# WiFly-BoosterPack-RevA1.net
KiCad netlist of a schematic drawn in EAGLE
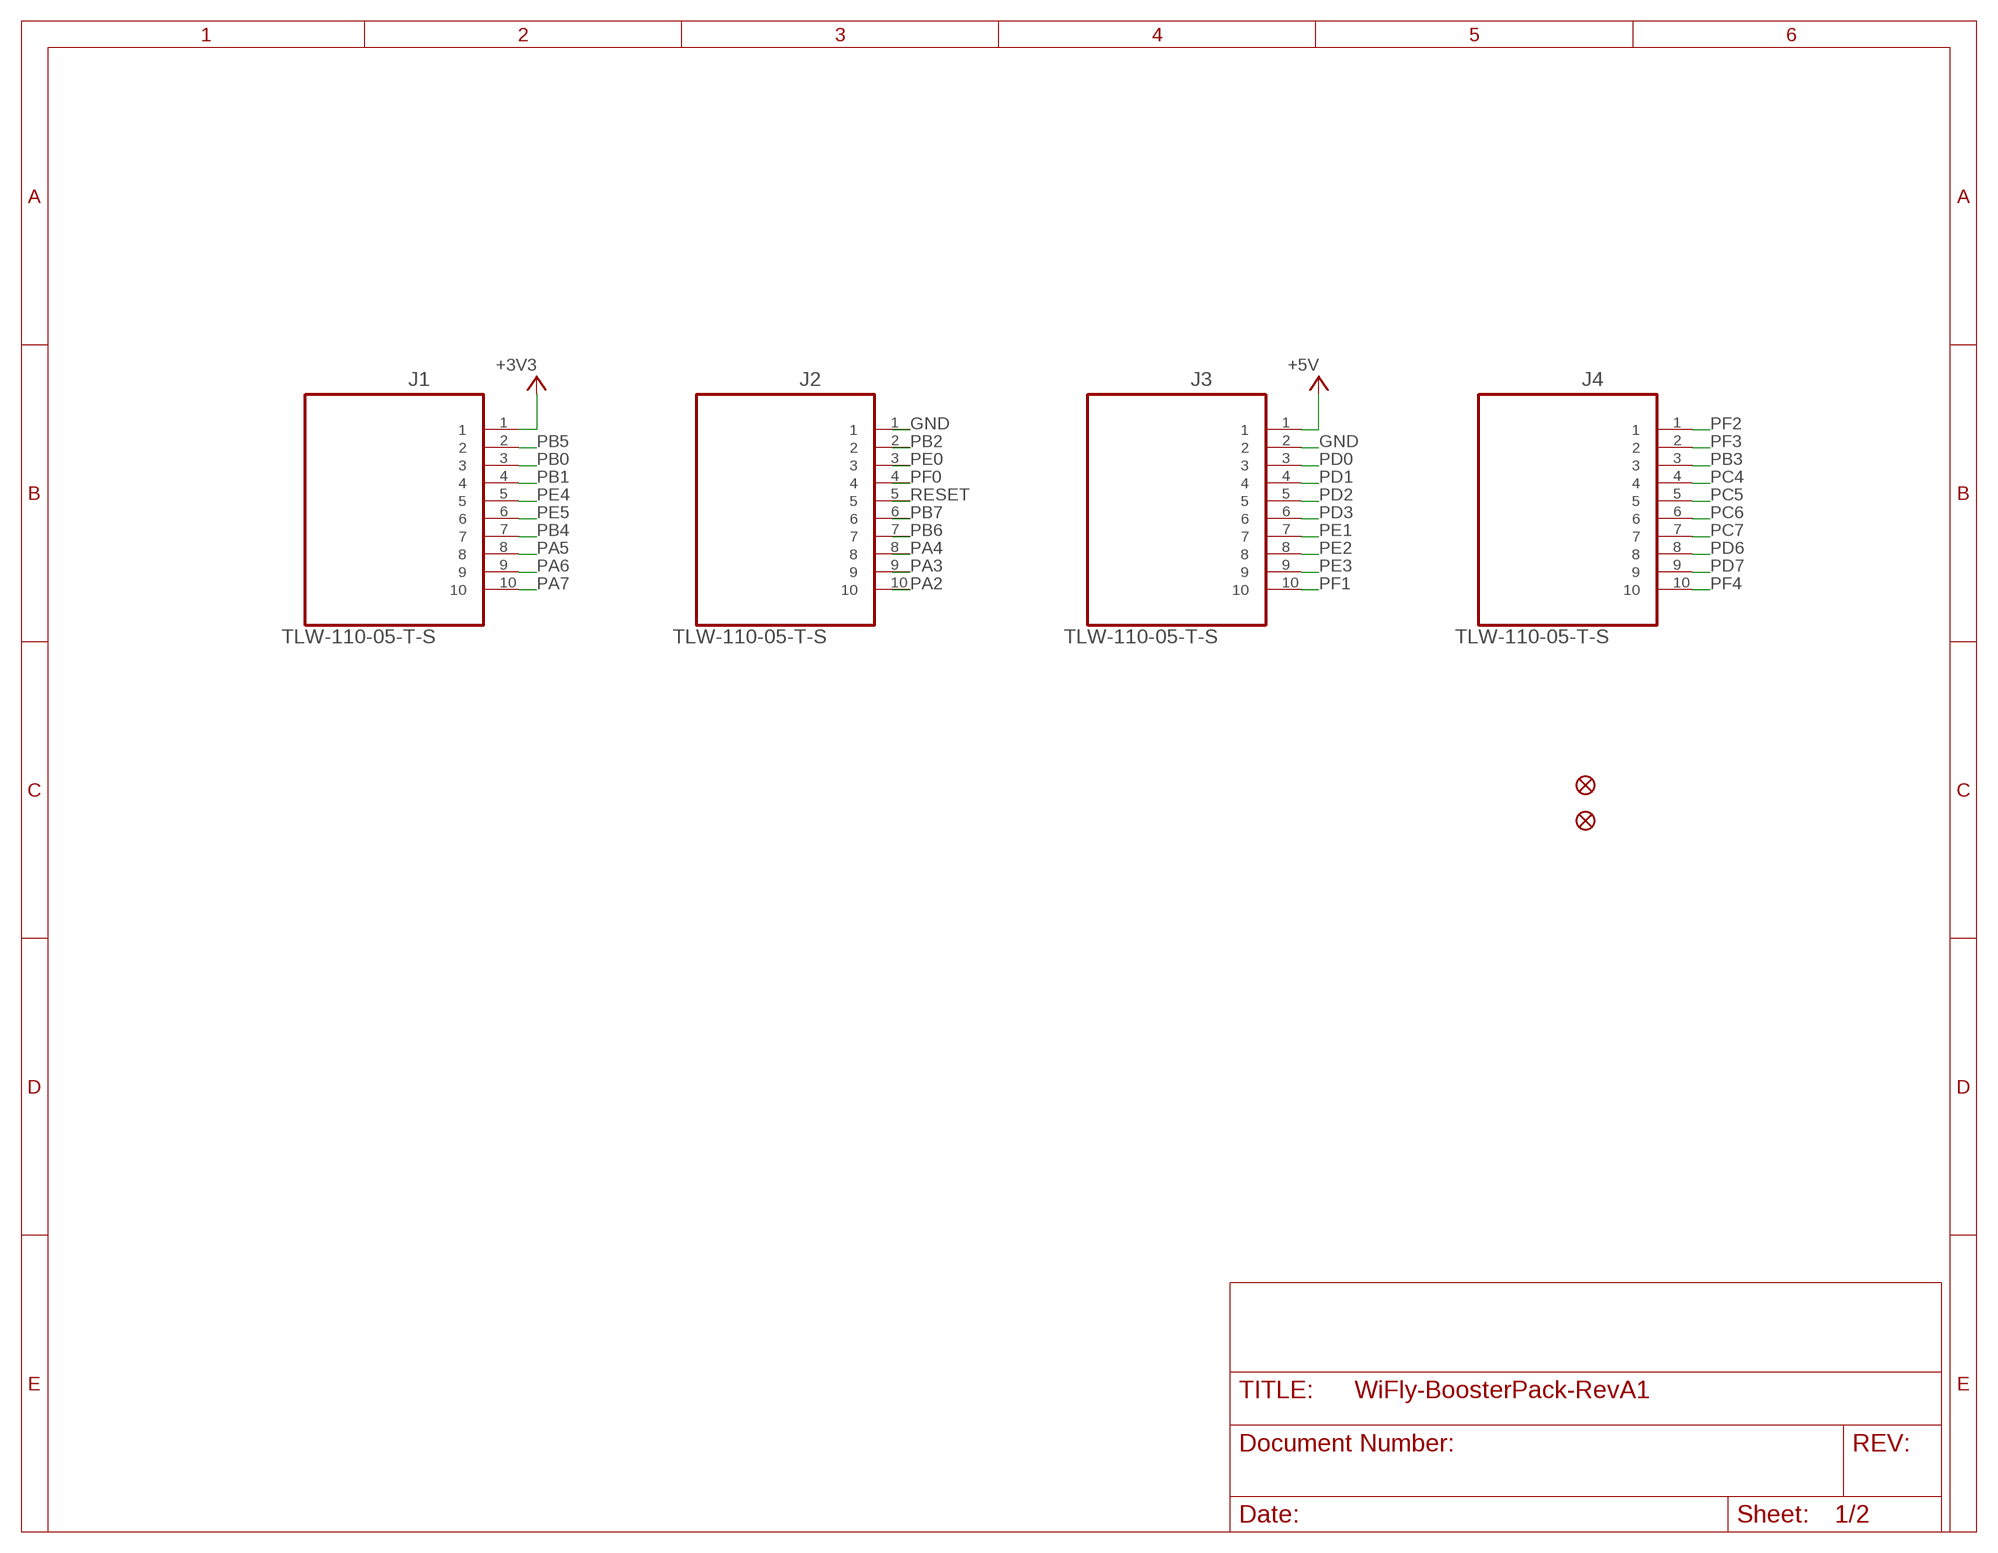
[diagram p0: schematic, sheet 1]
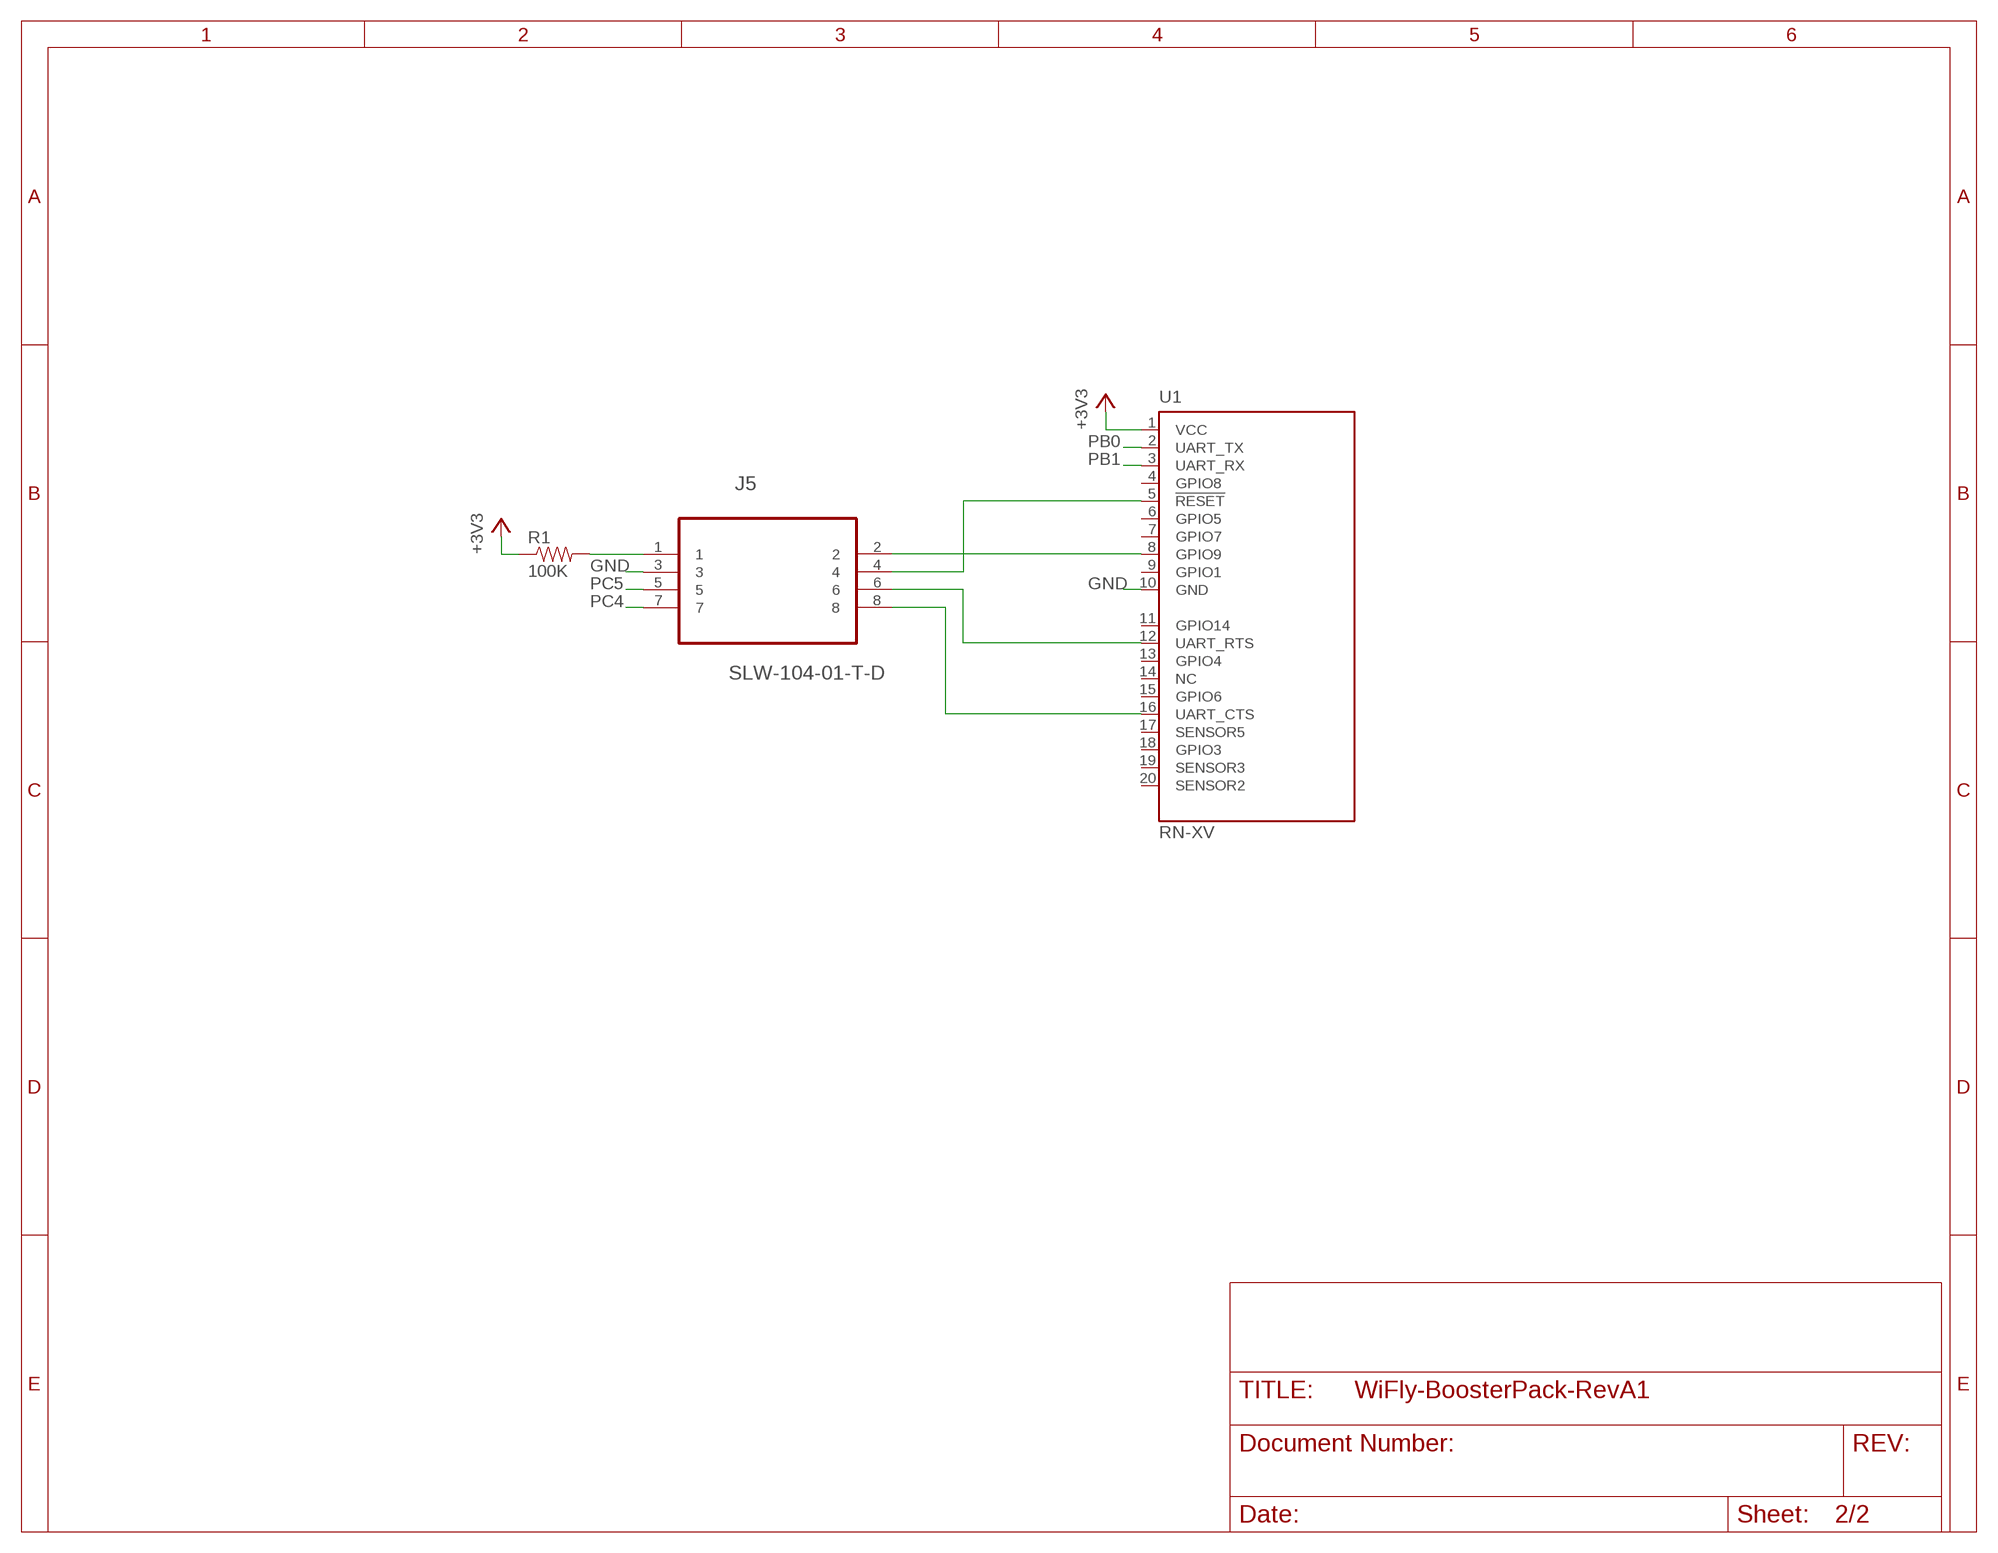
[diagram p1: schematic, sheet 2]

(export (version "E")
  (design (tool "Eeschema 10.0.6"))
  (components
    (comp (ref "FID1")
      (value "FIDUCIAL1X2")
      (footprint "eagle-import:FIDUCIAL-1X2")
      (libsource (lib "eagle-import") (part "FIDUCIAL1X2"))
    )
    (comp (ref "FID2")
      (value "FIDUCIAL1X2")
      (footprint "eagle-import:FIDUCIAL-1X2")
      (libsource (lib "eagle-import") (part "FIDUCIAL1X2"))
    )
    (comp (ref "J1")
      (value "TLW-110-05-T-S")
      (footprint "eagle-import:SAMTEC_TLW-110-05-T-S")
      (libsource (lib "eagle-import") (part "TLW-110-05-T-S"))
    )
    (comp (ref "J2")
      (value "TLW-110-05-T-S")
      (footprint "eagle-import:SAMTEC_TLW-110-05-T-S")
      (fields
        (field (name "MPN") "TLW-110-05-T-S")
        (field (name "OC_FARNELL") "-")
        (field (name "OC_NEWARK") "12P0439")
        (field (name "PACKAGE") "CONN HEADER 10 POS .100 inch")
        (field (name "SUPPLIER") "SAMTEC")
      )
      (libsource (lib "eagle-import") (part "TLW-110-05-T-S"))
    )
    (comp (ref "J3")
      (value "TLW-110-05-T-S")
      (footprint "eagle-import:SAMTEC_TLW-110-05-T-S")
      (fields
        (field (name "MPN") "TLW-110-05-T-S")
        (field (name "OC_FARNELL") "-")
        (field (name "OC_NEWARK") "12P0439")
        (field (name "PACKAGE") "CONN HEADER 10 POS .100 inch")
        (field (name "SUPPLIER") "SAMTEC")
      )
      (libsource (lib "eagle-import") (part "TLW-110-05-T-S"))
    )
    (comp (ref "J4")
      (value "TLW-110-05-T-S")
      (footprint "eagle-import:SAMTEC_TLW-110-05-T-S")
      (fields
        (field (name "MPN") "TLW-110-05-T-S")
        (field (name "OC_FARNELL") "-")
        (field (name "OC_NEWARK") "12P0439")
        (field (name "PACKAGE") "CONN HEADER 10 POS .100 inch")
        (field (name "SUPPLIER") "SAMTEC")
      )
      (libsource (lib "eagle-import") (part "TLW-110-05-T-S"))
    )
    (comp (ref "J5")
      (value "SLW-104-01-T-D")
      (footprint "eagle-import:SAMTEC_SLW-104-01-T-D")
      (libsource (lib "eagle-import") (part "SLW-104-01-T-D"))
    )
    (comp (ref "R1")
      (value "100K")
      (footprint "eagle-import:AXIAL-0.3")
      (libsource (lib "eagle-import") (part "RESISTORAXIAL-0.3"))
    )
    (comp (ref "U1")
      (value "RN-XV")
      (footprint "eagle-import:RN-VX")
      (libsource (lib "eagle-import") (part "RN-XV"))
    )
  )
  (nets
    (net (code "1") (name "+3V3") (class "Default")
      (node (ref "J1") (pin "1") (pinfunction "1_1") (pintype "passive"))
      (node (ref "R1") (pin "P$1") (pinfunction "1_P$1") (pintype "passive"))
      (node (ref "U1") (pin "1") (pinfunction "VCC_1") (pintype "power_in"))
    )
    (net (code "2") (name "+5V") (class "Default")
      (node (ref "J3") (pin "1") (pinfunction "1_1") (pintype "passive"))
    )
    (net (code "3") (name "GND") (class "Default")
      (node (ref "J2") (pin "1") (pinfunction "1_1") (pintype "passive"))
      (node (ref "J3") (pin "2") (pinfunction "2_2") (pintype "passive"))
      (node (ref "J5") (pin "3") (pinfunction "3_3") (pintype "passive"))
      (node (ref "U1") (pin "10") (pinfunction "GND_10") (pintype "power_in"))
    )
    (net (code "4") (name "Net-(R1-2)") (class "Default")
      (node (ref "J5") (pin "1") (pinfunction "1_1") (pintype "passive"))
      (node (ref "R1") (pin "P$2") (pinfunction "2_P$2") (pintype "passive"))
    )
    (net (code "5") (name "Net-(U1-GPIO9)") (class "Default")
      (node (ref "J5") (pin "2") (pinfunction "2_2") (pintype "passive"))
      (node (ref "U1") (pin "8") (pinfunction "GPIO9_8") (pintype "bidirectional"))
    )
    (net (code "6") (name "Net-(U1-UART_CTS)") (class "Default")
      (node (ref "J5") (pin "8") (pinfunction "8_8") (pintype "passive"))
      (node (ref "U1") (pin "16") (pinfunction "UART_CTS_16") (pintype "input"))
    )
    (net (code "7") (name "Net-(U1-UART_RTS)") (class "Default")
      (node (ref "J5") (pin "6") (pinfunction "6_6") (pintype "passive"))
      (node (ref "U1") (pin "12") (pinfunction "UART_RTS_12") (pintype "output"))
    )
    (net (code "8") (name "Net-(U1-~{RESET})") (class "Default")
      (node (ref "J5") (pin "4") (pinfunction "4_4") (pintype "passive"))
      (node (ref "U1") (pin "5") (pinfunction "~{RESET}_5") (pintype "input"))
    )
    (net (code "9") (name "PA2") (class "Default")
      (node (ref "J2") (pin "10") (pinfunction "10_10") (pintype "passive"))
    )
    (net (code "10") (name "PA3") (class "Default")
      (node (ref "J2") (pin "9") (pinfunction "9_9") (pintype "passive"))
    )
    (net (code "11") (name "PA4") (class "Default")
      (node (ref "J2") (pin "8") (pinfunction "8_8") (pintype "passive"))
    )
    (net (code "12") (name "PA5") (class "Default")
      (node (ref "J1") (pin "8") (pinfunction "8_8") (pintype "passive"))
    )
    (net (code "13") (name "PA6") (class "Default")
      (node (ref "J1") (pin "9") (pinfunction "9_9") (pintype "passive"))
    )
    (net (code "14") (name "PA7") (class "Default")
      (node (ref "J1") (pin "10") (pinfunction "10_10") (pintype "passive"))
    )
    (net (code "15") (name "PB0") (class "Default")
      (node (ref "J1") (pin "3") (pinfunction "3_3") (pintype "passive"))
      (node (ref "U1") (pin "2") (pinfunction "UART_TX_2") (pintype "output"))
    )
    (net (code "16") (name "PB1") (class "Default")
      (node (ref "J1") (pin "4") (pinfunction "4_4") (pintype "passive"))
      (node (ref "U1") (pin "3") (pinfunction "UART_RX_3") (pintype "input"))
    )
    (net (code "17") (name "PB2") (class "Default")
      (node (ref "J2") (pin "2") (pinfunction "2_2") (pintype "passive"))
    )
    (net (code "18") (name "PB3") (class "Default")
      (node (ref "J4") (pin "3") (pinfunction "3_3") (pintype "passive"))
    )
    (net (code "19") (name "PB4") (class "Default")
      (node (ref "J1") (pin "7") (pinfunction "7_7") (pintype "passive"))
    )
    (net (code "20") (name "PB5") (class "Default")
      (node (ref "J1") (pin "2") (pinfunction "2_2") (pintype "passive"))
    )
    (net (code "21") (name "PB6") (class "Default")
      (node (ref "J2") (pin "7") (pinfunction "7_7") (pintype "passive"))
    )
    (net (code "22") (name "PB7") (class "Default")
      (node (ref "J2") (pin "6") (pinfunction "6_6") (pintype "passive"))
    )
    (net (code "23") (name "PC4") (class "Default")
      (node (ref "J4") (pin "4") (pinfunction "4_4") (pintype "passive"))
      (node (ref "J5") (pin "7") (pinfunction "7_7") (pintype "passive"))
    )
    (net (code "24") (name "PC5") (class "Default")
      (node (ref "J4") (pin "5") (pinfunction "5_5") (pintype "passive"))
      (node (ref "J5") (pin "5") (pinfunction "5_5") (pintype "passive"))
    )
    (net (code "25") (name "PC6") (class "Default")
      (node (ref "J4") (pin "6") (pinfunction "6_6") (pintype "passive"))
    )
    (net (code "26") (name "PC7") (class "Default")
      (node (ref "J4") (pin "7") (pinfunction "7_7") (pintype "passive"))
    )
    (net (code "27") (name "PD0") (class "Default")
      (node (ref "J3") (pin "3") (pinfunction "3_3") (pintype "passive"))
    )
    (net (code "28") (name "PD1") (class "Default")
      (node (ref "J3") (pin "4") (pinfunction "4_4") (pintype "passive"))
    )
    (net (code "29") (name "PD2") (class "Default")
      (node (ref "J3") (pin "5") (pinfunction "5_5") (pintype "passive"))
    )
    (net (code "30") (name "PD3") (class "Default")
      (node (ref "J3") (pin "6") (pinfunction "6_6") (pintype "passive"))
    )
    (net (code "31") (name "PD6") (class "Default")
      (node (ref "J4") (pin "8") (pinfunction "8_8") (pintype "passive"))
    )
    (net (code "32") (name "PD7") (class "Default")
      (node (ref "J4") (pin "9") (pinfunction "9_9") (pintype "passive"))
    )
    (net (code "33") (name "PE0") (class "Default")
      (node (ref "J2") (pin "3") (pinfunction "3_3") (pintype "passive"))
    )
    (net (code "34") (name "PE1") (class "Default")
      (node (ref "J3") (pin "7") (pinfunction "7_7") (pintype "passive"))
    )
    (net (code "35") (name "PE2") (class "Default")
      (node (ref "J3") (pin "8") (pinfunction "8_8") (pintype "passive"))
    )
    (net (code "36") (name "PE3") (class "Default")
      (node (ref "J3") (pin "9") (pinfunction "9_9") (pintype "passive"))
    )
    (net (code "37") (name "PE4") (class "Default")
      (node (ref "J1") (pin "5") (pinfunction "5_5") (pintype "passive"))
    )
    (net (code "38") (name "PE5") (class "Default")
      (node (ref "J1") (pin "6") (pinfunction "6_6") (pintype "passive"))
    )
    (net (code "39") (name "PF0") (class "Default")
      (node (ref "J2") (pin "4") (pinfunction "4_4") (pintype "passive"))
    )
    (net (code "40") (name "PF1") (class "Default")
      (node (ref "J3") (pin "10") (pinfunction "10_10") (pintype "passive"))
    )
    (net (code "41") (name "PF2") (class "Default")
      (node (ref "J4") (pin "1") (pinfunction "1_1") (pintype "passive"))
    )
    (net (code "42") (name "PF3") (class "Default")
      (node (ref "J4") (pin "2") (pinfunction "2_2") (pintype "passive"))
    )
    (net (code "43") (name "PF4") (class "Default")
      (node (ref "J4") (pin "10") (pinfunction "10_10") (pintype "passive"))
    )
    (net (code "44") (name "RESET") (class "Default")
      (node (ref "J2") (pin "5") (pinfunction "5_5") (pintype "passive"))
    )
    (net (code "45") (name "unconnected-(U1-GPIO1-Pad9)") (class "Default")
      (node (ref "U1") (pin "9") (pinfunction "GPIO1_9") (pintype "bidirectional"))
    )
    (net (code "46") (name "unconnected-(U1-GPIO3-Pad18)") (class "Default")
      (node (ref "U1") (pin "18") (pinfunction "GPIO3_18") (pintype "bidirectional"))
    )
    (net (code "47") (name "unconnected-(U1-GPIO4-Pad13)") (class "Default")
      (node (ref "U1") (pin "13") (pinfunction "GPIO4_13") (pintype "bidirectional"))
    )
    (net (code "48") (name "unconnected-(U1-GPIO5-Pad6)") (class "Default")
      (node (ref "U1") (pin "6") (pinfunction "GPIO5_6") (pintype "output"))
    )
    (net (code "49") (name "unconnected-(U1-GPIO6-Pad15)") (class "Default")
      (node (ref "U1") (pin "15") (pinfunction "GPIO6_15") (pintype "bidirectional"))
    )
    (net (code "50") (name "unconnected-(U1-GPIO7-Pad7)") (class "Default")
      (node (ref "U1") (pin "7") (pinfunction "GPIO7_7") (pintype "bidirectional"))
    )
    (net (code "51") (name "unconnected-(U1-GPIO8-Pad4)") (class "Default")
      (node (ref "U1") (pin "4") (pinfunction "GPIO8_4") (pintype "bidirectional"))
    )
    (net (code "52") (name "unconnected-(U1-GPIO14-Pad11)") (class "Default")
      (node (ref "U1") (pin "11") (pinfunction "GPIO14_11") (pintype "bidirectional"))
    )
    (net (code "53") (name "unconnected-(U1-NC-Pad14)") (class "Default")
      (node (ref "U1") (pin "14") (pinfunction "NC_14") (pintype "no_connect"))
    )
    (net (code "54") (name "unconnected-(U1-SENSOR2-Pad20)") (class "Default")
      (node (ref "U1") (pin "20") (pinfunction "SENSOR2_20") (pintype "input"))
    )
    (net (code "55") (name "unconnected-(U1-SENSOR3-Pad19)") (class "Default")
      (node (ref "U1") (pin "19") (pinfunction "SENSOR3_19") (pintype "input"))
    )
    (net (code "56") (name "unconnected-(U1-SENSOR5-Pad17)") (class "Default")
      (node (ref "U1") (pin "17") (pinfunction "SENSOR5_17") (pintype "input"))
    )
  )
)
